# untitled.net
KiCad netlist of a schematic drawn in EAGLE
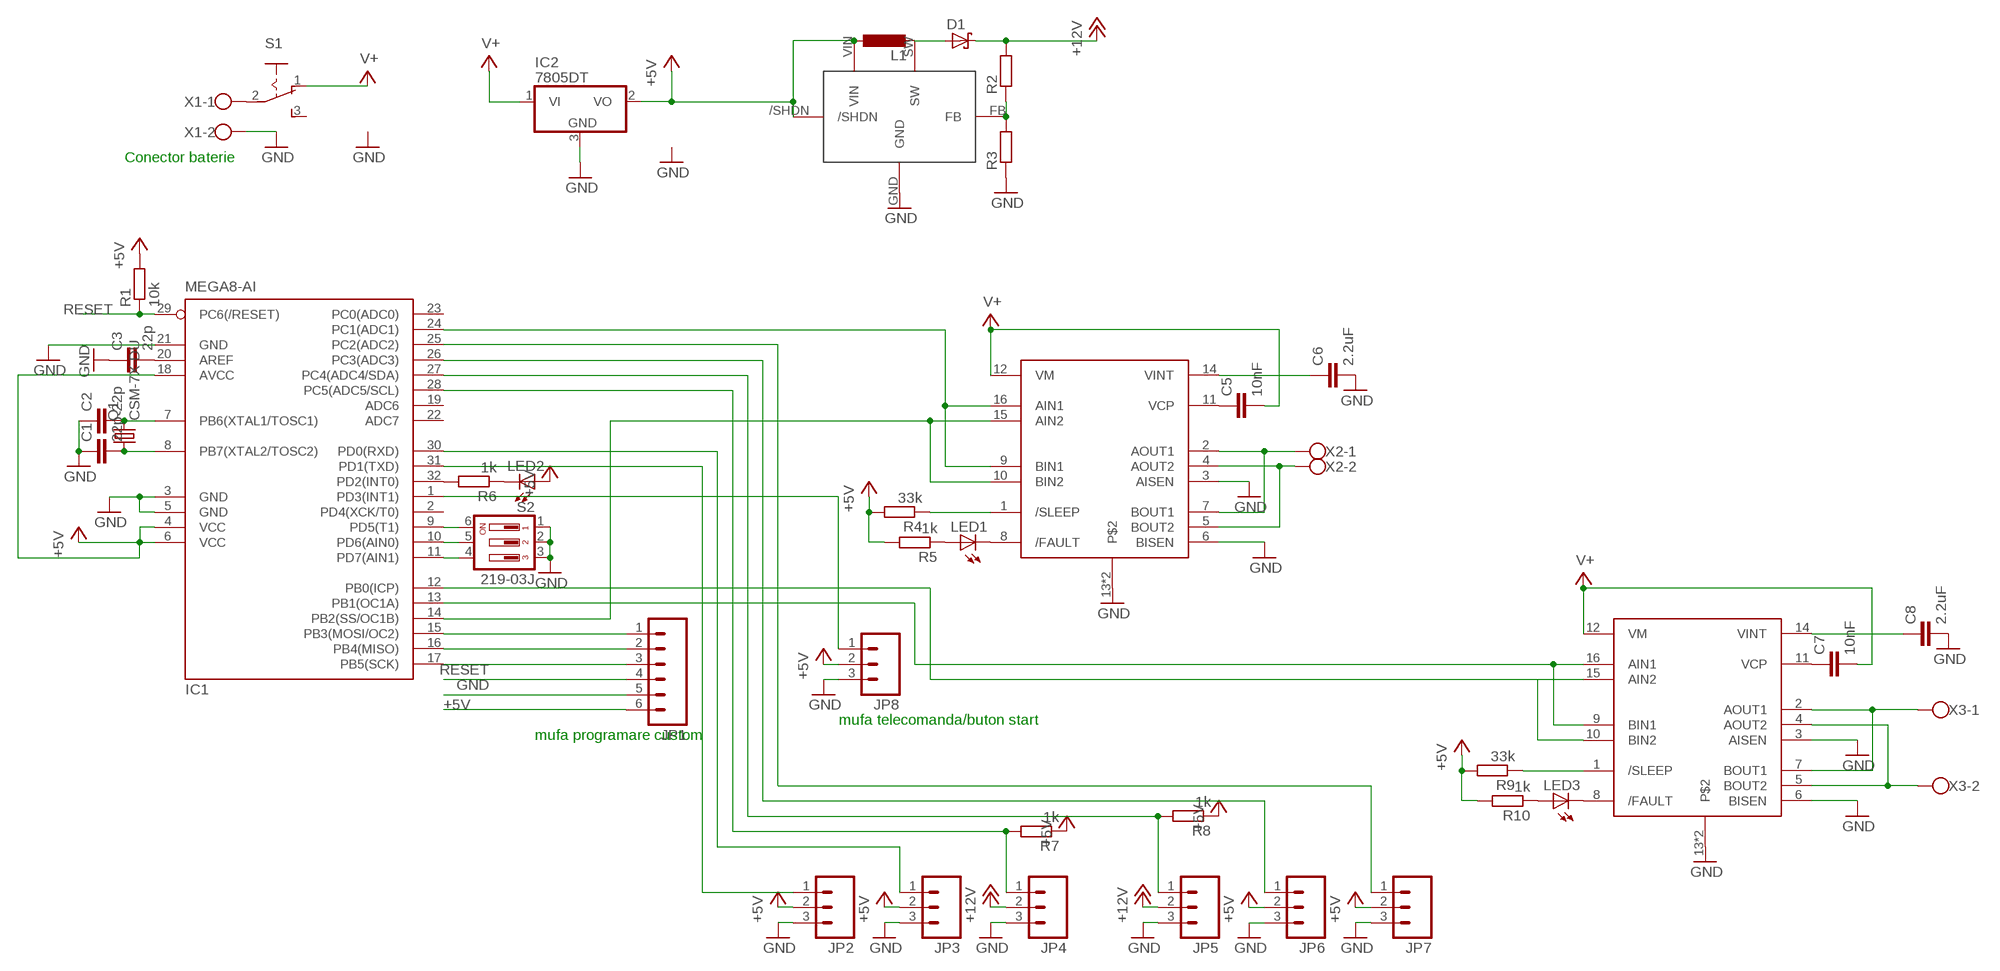
[diagram p0: schematic, sheet 1]

(export (version "E")
  (design (tool "Eeschema 10.0.6"))
  (components
    (comp (ref "C1")
      (value "22p")
      (footprint "eagle-import:C0805")
      (libsource (lib "eagle-import") (part "C-EUC0805"))
    )
    (comp (ref "C2")
      (value "22p")
      (footprint "eagle-import:C0805")
      (libsource (lib "eagle-import") (part "C-EUC0805"))
    )
    (comp (ref "C3")
      (value "22p")
      (footprint "eagle-import:C0805")
      (libsource (lib "eagle-import") (part "C-EUC0805"))
    )
    (comp (ref "C5")
      (value "10nF")
      (footprint "eagle-import:C0805")
      (libsource (lib "eagle-import") (part "C-EUC0805"))
    )
    (comp (ref "C6")
      (value "2.2uF")
      (footprint "eagle-import:C0805")
      (libsource (lib "eagle-import") (part "C-EUC0805"))
    )
    (comp (ref "C7")
      (value "10nF")
      (footprint "eagle-import:C0805")
      (libsource (lib "eagle-import") (part "C-EUC0805"))
    )
    (comp (ref "C8")
      (value "2.2uF")
      (footprint "eagle-import:C0805")
      (libsource (lib "eagle-import") (part "C-EUC0805"))
    )
    (comp (ref "D1")
      (value "SCHOTTKY-DIODESMD")
      (footprint "eagle-import:SMB")
      (libsource (lib "eagle-import") (part "SCHOTTKY-DIODESMD"))
    )
    (comp (ref "IC1")
      (value "MEGA8-AI")
      (footprint "eagle-import:TQFP32-08")
      (fields (field (name "MPN") "ATMEGA8-16AU"))
      (libsource (lib "eagle-import") (part "MEGA8-AI"))
    )
    (comp (ref "IC2")
      (value "7805DT")
      (footprint "eagle-import:TO252")
      (libsource (lib "eagle-import") (part "78DT05"))
    )
    (comp (ref "JP1")
      (value "M06SIP")
      (footprint "eagle-import:1X06")
      (libsource (lib "eagle-import") (part "M06SIP"))
    )
    (comp (ref "JP2")
      (value "M03PTH")
      (footprint "eagle-import:1X03")
      (libsource (lib "eagle-import") (part "M03PTH"))
    )
    (comp (ref "JP3")
      (value "M03PTH")
      (footprint "eagle-import:1X03")
      (libsource (lib "eagle-import") (part "M03PTH"))
    )
    (comp (ref "JP4")
      (value "M03PTH")
      (footprint "eagle-import:1X03")
      (libsource (lib "eagle-import") (part "M03PTH"))
    )
    (comp (ref "JP5")
      (value "M03PTH")
      (footprint "eagle-import:1X03")
      (libsource (lib "eagle-import") (part "M03PTH"))
    )
    (comp (ref "JP6")
      (value "M03PTH")
      (footprint "eagle-import:1X03")
      (libsource (lib "eagle-import") (part "M03PTH"))
    )
    (comp (ref "JP7")
      (value "M03PTH")
      (footprint "eagle-import:1X03")
      (libsource (lib "eagle-import") (part "M03PTH"))
    )
    (comp (ref "JP8")
      (value "M03PTH")
      (footprint "eagle-import:1X03")
      (libsource (lib "eagle-import") (part "M03PTH"))
    )
    (comp (ref "L1")
      (value "L-EUL4532C")
      (footprint "eagle-import:L4532M")
      (libsource (lib "eagle-import") (part "L-EUL4532C"))
    )
    (comp (ref "LED1")
      (value "LEDSML0805")
      (footprint "eagle-import:SML0805")
      (libsource (lib "eagle-import") (part "LEDSML0805"))
    )
    (comp (ref "LED2")
      (value "LEDSML0805")
      (footprint "eagle-import:SML0805")
      (libsource (lib "eagle-import") (part "LEDSML0805"))
    )
    (comp (ref "LED3")
      (value "LEDSML0805")
      (footprint "eagle-import:SML0805")
      (libsource (lib "eagle-import") (part "LEDSML0805"))
    )
    (comp (ref "Q1")
      (value "CSM-7X-DU")
      (footprint "eagle-import:CSM-7X-DU")
      (libsource (lib "eagle-import") (part "CSM-7X-DU"))
    )
    (comp (ref "R1")
      (value "10k")
      (footprint "eagle-import:R0805")
      (libsource (lib "eagle-import") (part "R-EU_R0805"))
    )
    (comp (ref "R2")
      (value "R-EU_R0805")
      (footprint "eagle-import:R0805")
      (libsource (lib "eagle-import") (part "R-EU_R0805"))
    )
    (comp (ref "R3")
      (value "R-EU_R0805")
      (footprint "eagle-import:R0805")
      (libsource (lib "eagle-import") (part "R-EU_R0805"))
    )
    (comp (ref "R4")
      (value "33k")
      (footprint "eagle-import:R0805")
      (libsource (lib "eagle-import") (part "R-EU_R0805"))
    )
    (comp (ref "R5")
      (value "1k")
      (footprint "eagle-import:R0805")
      (libsource (lib "eagle-import") (part "R-EU_R0805"))
    )
    (comp (ref "R6")
      (value "1k")
      (footprint "eagle-import:R0805")
      (libsource (lib "eagle-import") (part "R-EU_R0805"))
    )
    (comp (ref "R7")
      (value "1k")
      (footprint "eagle-import:R0805")
      (libsource (lib "eagle-import") (part "R-EU_R0805"))
    )
    (comp (ref "R8")
      (value "1k")
      (footprint "eagle-import:R0805")
      (libsource (lib "eagle-import") (part "R-EU_R0805"))
    )
    (comp (ref "R9")
      (value "33k")
      (footprint "eagle-import:R0805")
      (libsource (lib "eagle-import") (part "R-EU_R0805"))
    )
    (comp (ref "R10")
      (value "1k")
      (footprint "eagle-import:R0805")
      (libsource (lib "eagle-import") (part "R-EU_R0805"))
    )
    (comp (ref "S1")
      (value "255SB")
      (footprint "eagle-import:255SB")
      (libsource (lib "eagle-import") (part "255SB"))
    )
    (comp (ref "S2")
      (value "219-03J")
      (footprint "eagle-import:CTS-219-03J")
      (libsource (lib "eagle-import") (part "219-03J"))
    )
    (comp (ref "U$1")
      (value "LM2703")
      (footprint "eagle-import:SOT23")
      (libsource (lib "eagle-import") (part "LM2703"))
    )
    (comp (ref "U$2")
      (value "DRV8833-PWP")
      (footprint "eagle-import:PW")
      (libsource (lib "eagle-import") (part "DRV8833-PWP"))
    )
    (comp (ref "U$3")
      (value "DRV8833-PWP")
      (footprint "eagle-import:PW")
      (libsource (lib "eagle-import") (part "DRV8833-PWP"))
    )
    (comp (ref "X1")
      (value "W237-102")
      (footprint "eagle-import:W237-102")
      (fields (field (name "MPN") "237-102"))
      (libsource (lib "eagle-import") (part "W237-102"))
    )
    (comp (ref "X2")
      (value "W237-102")
      (footprint "eagle-import:W237-102")
      (fields (field (name "MPN") "237-102"))
      (libsource (lib "eagle-import") (part "W237-102"))
    )
    (comp (ref "X3")
      (value "W237-102")
      (footprint "eagle-import:W237-102")
      (fields (field (name "MPN") "237-102"))
      (libsource (lib "eagle-import") (part "W237-102"))
    )
  )
  (nets
    (net (code "1") (name "+5V") (class "Default")
      (node (ref "IC1") (pin "18") (pinfunction "AVCC_18") (pintype "power_in"))
      (node (ref "IC1") (pin "4") (pinfunction "VCC_4") (pintype "power_in"))
      (node (ref "IC1") (pin "6") (pinfunction "VCC_6") (pintype "power_in"))
      (node (ref "IC2") (pin "2") (pinfunction "VO_2") (pintype "passive"))
      (node (ref "JP1") (pin "6") (pinfunction "6_6") (pintype "passive"))
      (node (ref "JP2") (pin "2") (pinfunction "2_2") (pintype "passive"))
      (node (ref "JP3") (pin "2") (pinfunction "2_2") (pintype "passive"))
      (node (ref "JP6") (pin "2") (pinfunction "2_2") (pintype "passive"))
      (node (ref "JP7") (pin "2") (pinfunction "2_2") (pintype "passive"))
      (node (ref "JP8") (pin "2") (pinfunction "2_2") (pintype "passive"))
      (node (ref "L1") (pin "1") (pinfunction "1_1") (pintype "passive"))
      (node (ref "LED2") (pin "A") (pinfunction "A_A") (pintype "passive"))
      (node (ref "R1") (pin "2") (pinfunction "2_2") (pintype "passive"))
      (node (ref "R10") (pin "2") (pinfunction "2_2") (pintype "passive"))
      (node (ref "R4") (pin "2") (pinfunction "2_2") (pintype "passive"))
      (node (ref "R5") (pin "2") (pinfunction "2_2") (pintype "passive"))
      (node (ref "R7") (pin "1") (pinfunction "1_1") (pintype "passive"))
      (node (ref "R8") (pin "1") (pinfunction "1_1") (pintype "passive"))
      (node (ref "R9") (pin "2") (pinfunction "2_2") (pintype "passive"))
      (node (ref "U$1") (pin "/SHDN") (pinfunction "/SHDN_/SHDN") (pintype "bidirectional"))
      (node (ref "U$1") (pin "VIN") (pinfunction "VIN_VIN") (pintype "bidirectional"))
    )
    (net (code "2") (name "+12V") (class "Default")
      (node (ref "D1") (pin "C") (pinfunction "C_C") (pintype "passive"))
      (node (ref "JP4") (pin "2") (pinfunction "2_2") (pintype "passive"))
      (node (ref "JP5") (pin "2") (pinfunction "2_2") (pintype "passive"))
      (node (ref "R2") (pin "2") (pinfunction "2_2") (pintype "passive"))
    )
    (net (code "3") (name "/RESET") (class "Default")
      (node (ref "IC1") (pin "29") (pinfunction "PC6(/RESET)_29") (pintype "bidirectional"))
      (node (ref "JP1") (pin "4") (pinfunction "4_4") (pintype "passive"))
      (node (ref "R1") (pin "1") (pinfunction "1_1") (pintype "passive"))
    )
    (net (code "4") (name "GND") (class "Default")
      (node (ref "C1") (pin "1") (pinfunction "1_1") (pintype "passive"))
      (node (ref "C2") (pin "1") (pinfunction "1_1") (pintype "passive"))
      (node (ref "C3") (pin "1") (pinfunction "1_1") (pintype "passive"))
      (node (ref "C6") (pin "2") (pinfunction "2_2") (pintype "passive"))
      (node (ref "C8") (pin "2") (pinfunction "2_2") (pintype "passive"))
      (node (ref "IC1") (pin "21") (pinfunction "GND_21") (pintype "power_in"))
      (node (ref "IC1") (pin "3") (pinfunction "GND_3") (pintype "power_in"))
      (node (ref "IC1") (pin "5") (pinfunction "GND_5") (pintype "power_in"))
      (node (ref "IC2") (pin "3") (pinfunction "GND_3") (pintype "passive"))
      (node (ref "JP1") (pin "5") (pinfunction "5_5") (pintype "passive"))
      (node (ref "JP2") (pin "3") (pinfunction "3_3") (pintype "passive"))
      (node (ref "JP3") (pin "3") (pinfunction "3_3") (pintype "passive"))
      (node (ref "JP4") (pin "3") (pinfunction "3_3") (pintype "passive"))
      (node (ref "JP5") (pin "3") (pinfunction "3_3") (pintype "passive"))
      (node (ref "JP6") (pin "3") (pinfunction "3_3") (pintype "passive"))
      (node (ref "JP7") (pin "3") (pinfunction "3_3") (pintype "passive"))
      (node (ref "JP8") (pin "3") (pinfunction "3_3") (pintype "passive"))
      (node (ref "R3") (pin "1") (pinfunction "1_1") (pintype "passive"))
      (node (ref "S2") (pin "1") (pinfunction "1_1") (pintype "passive"))
      (node (ref "S2") (pin "2") (pinfunction "2_2") (pintype "passive"))
      (node (ref "S2") (pin "3") (pinfunction "3_3") (pintype "passive"))
      (node (ref "U$1") (pin "GND") (pinfunction "GND_GND") (pintype "bidirectional"))
      (node (ref "U$2") (pin "13") (pinfunction "P$2_13") (pintype "bidirectional"))
      (node (ref "U$2") (pin "3") (pinfunction "AISEN_3") (pintype "bidirectional"))
      (node (ref "U$2") (pin "6") (pinfunction "BISEN_6") (pintype "bidirectional"))
      (node (ref "U$2") (pin "PAD") (pinfunction "P$2_PAD") (pintype "bidirectional"))
      (node (ref "U$3") (pin "13") (pinfunction "P$2_13") (pintype "bidirectional"))
      (node (ref "U$3") (pin "3") (pinfunction "AISEN_3") (pintype "bidirectional"))
      (node (ref "U$3") (pin "6") (pinfunction "BISEN_6") (pintype "bidirectional"))
      (node (ref "U$3") (pin "PAD") (pinfunction "P$2_PAD") (pintype "bidirectional"))
      (node (ref "X1") (pin "2") (pinfunction "KL_2") (pintype "passive"))
    )
    (net (code "5") (name "Net-(D1-PadA)") (class "Default")
      (node (ref "D1") (pin "A") (pinfunction "A_A") (pintype "passive"))
      (node (ref "L1") (pin "2") (pinfunction "2_2") (pintype "passive"))
      (node (ref "U$1") (pin "SW") (pinfunction "SW_SW") (pintype "bidirectional"))
    )
    (net (code "6") (name "Net-(IC1-AREF)") (class "Default")
      (node (ref "C3") (pin "2") (pinfunction "2_2") (pintype "passive"))
      (node (ref "IC1") (pin "20") (pinfunction "AREF_20") (pintype "passive"))
    )
    (net (code "7") (name "Net-(IC1-PB0(ICP))") (class "Default")
      (node (ref "IC1") (pin "12") (pinfunction "PB0(ICP)_12") (pintype "bidirectional"))
      (node (ref "U$3") (pin "10") (pinfunction "BIN2_10") (pintype "bidirectional"))
      (node (ref "U$3") (pin "15") (pinfunction "AIN2_15") (pintype "bidirectional"))
    )
    (net (code "8") (name "Net-(IC1-PB1(OC1A))") (class "Default")
      (node (ref "IC1") (pin "13") (pinfunction "PB1(OC1A)_13") (pintype "bidirectional"))
      (node (ref "U$3") (pin "16") (pinfunction "AIN1_16") (pintype "bidirectional"))
      (node (ref "U$3") (pin "9") (pinfunction "BIN1_9") (pintype "bidirectional"))
    )
    (net (code "9") (name "Net-(IC1-PB2(SS{slash}OC1B))") (class "Default")
      (node (ref "IC1") (pin "14") (pinfunction "PB2(SS/OC1B)_14") (pintype "bidirectional"))
      (node (ref "U$2") (pin "10") (pinfunction "BIN2_10") (pintype "bidirectional"))
      (node (ref "U$2") (pin "15") (pinfunction "AIN2_15") (pintype "bidirectional"))
    )
    (net (code "10") (name "Net-(IC1-PB3(MOSI{slash}OC2))") (class "Default")
      (node (ref "IC1") (pin "15") (pinfunction "PB3(MOSI/OC2)_15") (pintype "bidirectional"))
      (node (ref "JP1") (pin "1") (pinfunction "1_1") (pintype "passive"))
    )
    (net (code "11") (name "Net-(IC1-PB4(MISO))") (class "Default")
      (node (ref "IC1") (pin "16") (pinfunction "PB4(MISO)_16") (pintype "bidirectional"))
      (node (ref "JP1") (pin "2") (pinfunction "2_2") (pintype "passive"))
    )
    (net (code "12") (name "Net-(IC1-PB5(SCK))") (class "Default")
      (node (ref "IC1") (pin "17") (pinfunction "PB5(SCK)_17") (pintype "bidirectional"))
      (node (ref "JP1") (pin "3") (pinfunction "3_3") (pintype "passive"))
    )
    (net (code "13") (name "Net-(IC1-PB6(XTAL1{slash}TOSC1))") (class "Default")
      (node (ref "C2") (pin "2") (pinfunction "2_2") (pintype "passive"))
      (node (ref "IC1") (pin "7") (pinfunction "PB6(XTAL1/TOSC1)_7") (pintype "bidirectional"))
      (node (ref "Q1") (pin "2") (pinfunction "2_2") (pintype "passive"))
    )
    (net (code "14") (name "Net-(IC1-PB7(XTAL2{slash}TOSC2))") (class "Default")
      (node (ref "C1") (pin "2") (pinfunction "2_2") (pintype "passive"))
      (node (ref "IC1") (pin "8") (pinfunction "PB7(XTAL2/TOSC2)_8") (pintype "bidirectional"))
      (node (ref "Q1") (pin "1") (pinfunction "1_1") (pintype "passive"))
    )
    (net (code "15") (name "Net-(IC1-PC1(ADC1))") (class "Default")
      (node (ref "IC1") (pin "24") (pinfunction "PC1(ADC1)_24") (pintype "bidirectional"))
      (node (ref "U$2") (pin "16") (pinfunction "AIN1_16") (pintype "bidirectional"))
      (node (ref "U$2") (pin "9") (pinfunction "BIN1_9") (pintype "bidirectional"))
    )
    (net (code "16") (name "Net-(IC1-PC2(ADC2))") (class "Default")
      (node (ref "IC1") (pin "25") (pinfunction "PC2(ADC2)_25") (pintype "bidirectional"))
      (node (ref "JP7") (pin "1") (pinfunction "1_1") (pintype "passive"))
    )
    (net (code "17") (name "Net-(IC1-PC3(ADC3))") (class "Default")
      (node (ref "IC1") (pin "26") (pinfunction "PC3(ADC3)_26") (pintype "bidirectional"))
      (node (ref "JP6") (pin "1") (pinfunction "1_1") (pintype "passive"))
    )
    (net (code "18") (name "Net-(IC1-PC4(ADC4{slash}SDA))") (class "Default")
      (node (ref "IC1") (pin "27") (pinfunction "PC4(ADC4/SDA)_27") (pintype "bidirectional"))
      (node (ref "JP5") (pin "1") (pinfunction "1_1") (pintype "passive"))
      (node (ref "R8") (pin "2") (pinfunction "2_2") (pintype "passive"))
    )
    (net (code "19") (name "Net-(IC1-PC5(ADC5{slash}SCL))") (class "Default")
      (node (ref "IC1") (pin "28") (pinfunction "PC5(ADC5/SCL)_28") (pintype "bidirectional"))
      (node (ref "JP4") (pin "1") (pinfunction "1_1") (pintype "passive"))
      (node (ref "R7") (pin "2") (pinfunction "2_2") (pintype "passive"))
    )
    (net (code "20") (name "Net-(IC1-PD0(RXD))") (class "Default")
      (node (ref "IC1") (pin "30") (pinfunction "PD0(RXD)_30") (pintype "bidirectional"))
      (node (ref "JP3") (pin "1") (pinfunction "1_1") (pintype "passive"))
    )
    (net (code "21") (name "Net-(IC1-PD1(TXD))") (class "Default")
      (node (ref "IC1") (pin "31") (pinfunction "PD1(TXD)_31") (pintype "bidirectional"))
      (node (ref "JP2") (pin "1") (pinfunction "1_1") (pintype "passive"))
    )
    (net (code "22") (name "Net-(IC1-PD2(INT0))") (class "Default")
      (node (ref "IC1") (pin "32") (pinfunction "PD2(INT0)_32") (pintype "bidirectional"))
      (node (ref "R6") (pin "2") (pinfunction "2_2") (pintype "passive"))
    )
    (net (code "23") (name "Net-(IC1-PD3(INT1))") (class "Default")
      (node (ref "IC1") (pin "1") (pinfunction "PD3(INT1)_1") (pintype "bidirectional"))
      (node (ref "JP8") (pin "1") (pinfunction "1_1") (pintype "passive"))
    )
    (net (code "24") (name "Net-(IC1-PD5(T1))") (class "Default")
      (node (ref "IC1") (pin "9") (pinfunction "PD5(T1)_9") (pintype "bidirectional"))
      (node (ref "S2") (pin "6") (pinfunction "6_6") (pintype "passive"))
    )
    (net (code "25") (name "Net-(IC1-PD6(AIN0))") (class "Default")
      (node (ref "IC1") (pin "10") (pinfunction "PD6(AIN0)_10") (pintype "bidirectional"))
      (node (ref "S2") (pin "5") (pinfunction "5_5") (pintype "passive"))
    )
    (net (code "26") (name "Net-(IC1-PD7(AIN1))") (class "Default")
      (node (ref "IC1") (pin "11") (pinfunction "PD7(AIN1)_11") (pintype "bidirectional"))
      (node (ref "S2") (pin "4") (pinfunction "4_4") (pintype "passive"))
    )
    (net (code "27") (name "Net-(LED1-PadA)") (class "Default")
      (node (ref "LED1") (pin "A") (pinfunction "A_A") (pintype "passive"))
      (node (ref "R5") (pin "1") (pinfunction "1_1") (pintype "passive"))
    )
    (net (code "28") (name "Net-(LED2-PadC)") (class "Default")
      (node (ref "LED2") (pin "C") (pinfunction "C_C") (pintype "passive"))
      (node (ref "R6") (pin "1") (pinfunction "1_1") (pintype "passive"))
    )
    (net (code "29") (name "Net-(LED3-PadA)") (class "Default")
      (node (ref "LED3") (pin "A") (pinfunction "A_A") (pintype "passive"))
      (node (ref "R10") (pin "1") (pinfunction "1_1") (pintype "passive"))
    )
    (net (code "30") (name "Net-(R2-Pad1)") (class "Default")
      (node (ref "R2") (pin "1") (pinfunction "1_1") (pintype "passive"))
      (node (ref "R3") (pin "2") (pinfunction "2_2") (pintype "passive"))
      (node (ref "U$1") (pin "FB") (pinfunction "FB_FB") (pintype "bidirectional"))
    )
    (net (code "31") (name "Net-(S1-P)") (class "Default")
      (node (ref "S1") (pin "2") (pinfunction "P_2") (pintype "passive"))
      (node (ref "X1") (pin "1") (pinfunction "KL_1") (pintype "passive"))
    )
    (net (code "32") (name "Net-(U$2-AOUT1)") (class "Default")
      (node (ref "U$2") (pin "2") (pinfunction "AOUT1_2") (pintype "bidirectional"))
      (node (ref "U$2") (pin "7") (pinfunction "BOUT1_7") (pintype "bidirectional"))
      (node (ref "X2") (pin "1") (pinfunction "KL_1") (pintype "passive"))
    )
    (net (code "33") (name "Net-(U$2-AOUT2)") (class "Default")
      (node (ref "U$2") (pin "4") (pinfunction "AOUT2_4") (pintype "bidirectional"))
      (node (ref "U$2") (pin "5") (pinfunction "BOUT2_5") (pintype "bidirectional"))
      (node (ref "X2") (pin "2") (pinfunction "KL_2") (pintype "passive"))
    )
    (net (code "34") (name "Net-(U$2-VCP)") (class "Default")
      (node (ref "C5") (pin "1") (pinfunction "1_1") (pintype "passive"))
      (node (ref "U$2") (pin "11") (pinfunction "VCP_11") (pintype "bidirectional"))
    )
    (net (code "35") (name "Net-(U$2-VINT)") (class "Default")
      (node (ref "C6") (pin "1") (pinfunction "1_1") (pintype "passive"))
      (node (ref "U$2") (pin "14") (pinfunction "VINT_14") (pintype "bidirectional"))
    )
    (net (code "36") (name "Net-(U$2-{slash}FAULT)") (class "Default")
      (node (ref "LED1") (pin "C") (pinfunction "C_C") (pintype "passive"))
      (node (ref "U$2") (pin "8") (pinfunction "/FAULT_8") (pintype "bidirectional"))
    )
    (net (code "37") (name "Net-(U$2-{slash}SLEEP)") (class "Default")
      (node (ref "R4") (pin "1") (pinfunction "1_1") (pintype "passive"))
      (node (ref "U$2") (pin "1") (pinfunction "/SLEEP_1") (pintype "bidirectional"))
    )
    (net (code "38") (name "Net-(U$3-AOUT1)") (class "Default")
      (node (ref "U$3") (pin "2") (pinfunction "AOUT1_2") (pintype "bidirectional"))
      (node (ref "U$3") (pin "7") (pinfunction "BOUT1_7") (pintype "bidirectional"))
      (node (ref "X3") (pin "1") (pinfunction "KL_1") (pintype "passive"))
    )
    (net (code "39") (name "Net-(U$3-AOUT2)") (class "Default")
      (node (ref "U$3") (pin "4") (pinfunction "AOUT2_4") (pintype "bidirectional"))
      (node (ref "U$3") (pin "5") (pinfunction "BOUT2_5") (pintype "bidirectional"))
      (node (ref "X3") (pin "2") (pinfunction "KL_2") (pintype "passive"))
    )
    (net (code "40") (name "Net-(U$3-VCP)") (class "Default")
      (node (ref "C7") (pin "1") (pinfunction "1_1") (pintype "passive"))
      (node (ref "U$3") (pin "11") (pinfunction "VCP_11") (pintype "bidirectional"))
    )
    (net (code "41") (name "Net-(U$3-VINT)") (class "Default")
      (node (ref "C8") (pin "1") (pinfunction "1_1") (pintype "passive"))
      (node (ref "U$3") (pin "14") (pinfunction "VINT_14") (pintype "bidirectional"))
    )
    (net (code "42") (name "Net-(U$3-{slash}FAULT)") (class "Default")
      (node (ref "LED3") (pin "C") (pinfunction "C_C") (pintype "passive"))
      (node (ref "U$3") (pin "8") (pinfunction "/FAULT_8") (pintype "bidirectional"))
    )
    (net (code "43") (name "Net-(U$3-{slash}SLEEP)") (class "Default")
      (node (ref "R9") (pin "1") (pinfunction "1_1") (pintype "passive"))
      (node (ref "U$3") (pin "1") (pinfunction "/SLEEP_1") (pintype "bidirectional"))
    )
    (net (code "44") (name "V+") (class "Default")
      (node (ref "C5") (pin "2") (pinfunction "2_2") (pintype "passive"))
      (node (ref "C7") (pin "2") (pinfunction "2_2") (pintype "passive"))
      (node (ref "IC2") (pin "1") (pinfunction "VI_1") (pintype "input"))
      (node (ref "S1") (pin "1") (pinfunction "O_1") (pintype "passive"))
      (node (ref "U$2") (pin "12") (pinfunction "VM_12") (pintype "bidirectional"))
      (node (ref "U$3") (pin "12") (pinfunction "VM_12") (pintype "bidirectional"))
    )
    (net (code "45") (name "unconnected-(IC1-ADC6-Pad19)") (class "Default")
      (node (ref "IC1") (pin "19") (pinfunction "ADC6_19") (pintype "bidirectional"))
    )
    (net (code "46") (name "unconnected-(IC1-ADC7-Pad22)") (class "Default")
      (node (ref "IC1") (pin "22") (pinfunction "ADC7_22") (pintype "bidirectional"))
    )
    (net (code "47") (name "unconnected-(IC1-PC0(ADC0)-Pad23)") (class "Default")
      (node (ref "IC1") (pin "23") (pinfunction "PC0(ADC0)_23") (pintype "bidirectional"))
    )
    (net (code "48") (name "unconnected-(IC1-PD4(XCK{slash}T0)-Pad2)") (class "Default")
      (node (ref "IC1") (pin "2") (pinfunction "PD4(XCK/T0)_2") (pintype "bidirectional"))
    )
    (net (code "49") (name "unconnected-(S1-S-Pad3)") (class "Default")
      (node (ref "S1") (pin "3") (pinfunction "S_3") (pintype "passive"))
    )
  )
)
